# BSPD.net
KiCad netlist of a schematic drawn in EAGLE
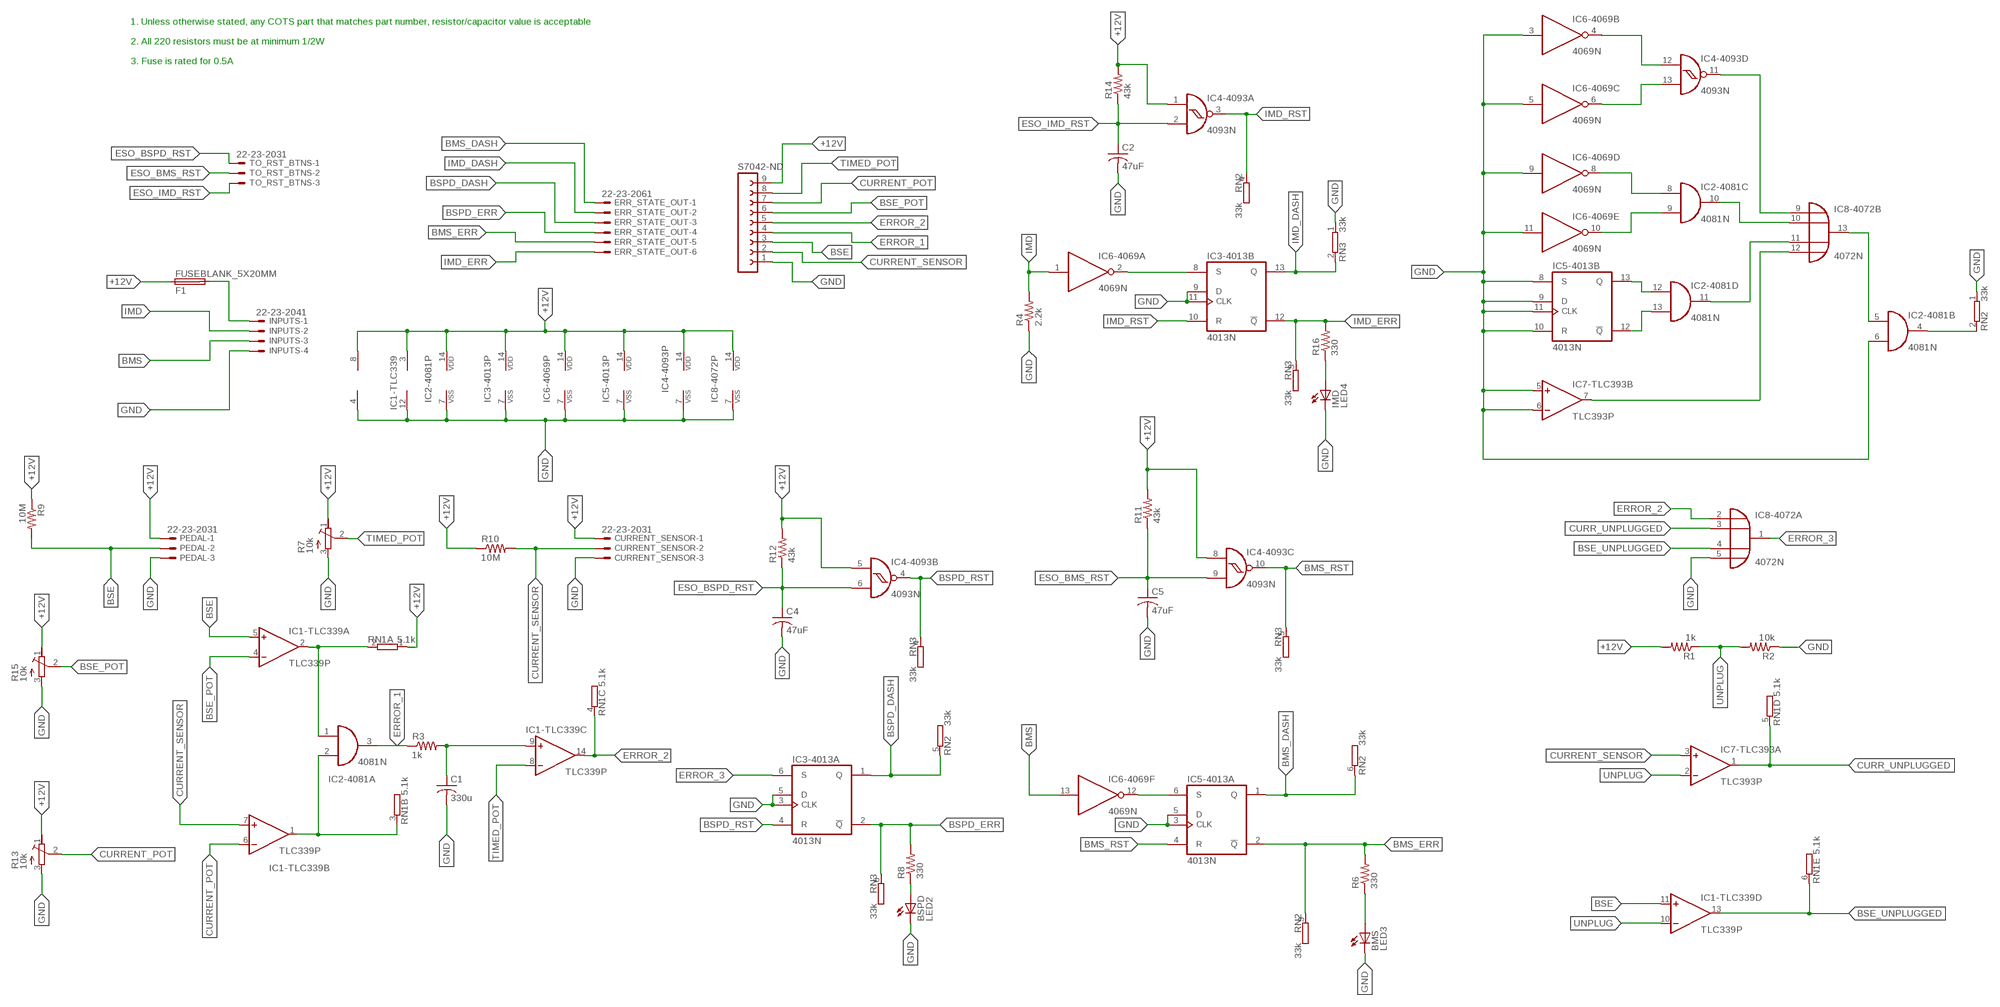
[diagram p0: schematic, sheet 1]

(export (version "E")
  (design (tool "Eeschema 10.0.6"))
  (components
    (comp (ref "BMS")
      (value "LED3")
      (footprint "eagle-import:LED3MM")
      (libsource (lib "eagle-import") (part "LED3MM"))
    )
    (comp (ref "BSPD")
      (value "LED2")
      (footprint "eagle-import:LED3MM")
      (libsource (lib "eagle-import") (part "LED3MM"))
    )
    (comp (ref "C1")
      (value "330u")
      (footprint "eagle-import:C225-108X268")
      (libsource (lib "eagle-import") (part "C-US225-108X268"))
    )
    (comp (ref "C2")
      (value "47uF")
      (footprint "eagle-import:C050-024X044")
      (libsource (lib "eagle-import") (part "C-US050-024X044"))
    )
    (comp (ref "C4")
      (value "47uF")
      (footprint "eagle-import:C050-024X044")
      (libsource (lib "eagle-import") (part "C-US050-024X044"))
    )
    (comp (ref "C5")
      (value "47uF")
      (footprint "eagle-import:C050-024X044")
      (libsource (lib "eagle-import") (part "C-US050-024X044"))
    )
    (comp (ref "CURRENT_SENSOR")
      (value "22-23-2031")
      (footprint "eagle-import:22-23-2031")
      (fields (field (name "MF") "MOLEX"))
      (libsource (lib "eagle-import") (part "22-23-2031"))
    )
    (comp (ref "ERR_STATE_OUT")
      (value "22-23-2061")
      (footprint "eagle-import:22-23-2061")
      (fields (field (name "MF") "MOLEX"))
      (libsource (lib "eagle-import") (part "22-23-2061"))
    )
    (comp (ref "F1")
      (value "FUSEBLANK_5X20MM")
      (footprint "eagle-import:FUSE_HOLDER_5X20MM")
      (libsource (lib "eagle-import") (part "FUSEBLANK_5X20MM"))
    )
    (comp (ref "IC1-TLC339")
      (value "TLC339P")
      (footprint "eagle-import:DIL14")
      (libsource (lib "eagle-import") (part "TLC339P"))
    )
    (comp (ref "IC2-4081")
      (value "4081N")
      (footprint "eagle-import:DIL14")
      (libsource (lib "eagle-import") (part "4081N"))
    )
    (comp (ref "IC3-4013")
      (value "4013N")
      (footprint "eagle-import:DIL14")
      (libsource (lib "eagle-import") (part "4013N"))
    )
    (comp (ref "IC4-4093")
      (value "4093N")
      (footprint "eagle-import:DIL14")
      (libsource (lib "eagle-import") (part "4093N"))
    )
    (comp (ref "IC5-4013")
      (value "4013N")
      (footprint "eagle-import:DIL14")
      (libsource (lib "eagle-import") (part "4013N"))
    )
    (comp (ref "IC6-4069")
      (value "4069N")
      (footprint "eagle-import:DIL14")
      (libsource (lib "eagle-import") (part "4069N"))
    )
    (comp (ref "IC7-TLC393")
      (value "TLC393P")
      (footprint "eagle-import:DIL08")
      (libsource (lib "eagle-import") (part "TLC393P"))
    )
    (comp (ref "IC8-4072")
      (value "4072N")
      (footprint "eagle-import:DIL14")
      (libsource (lib "eagle-import") (part "4072N"))
    )
    (comp (ref "IMD")
      (value "LED4")
      (footprint "eagle-import:LED3MM")
      (libsource (lib "eagle-import") (part "LED3MM"))
    )
    (comp (ref "INPUTS")
      (value "22-23-2041")
      (footprint "eagle-import:22-23-2041")
      (fields (field (name "MF") "MOLEX"))
      (libsource (lib "eagle-import") (part "22-23-2041"))
    )
    (comp (ref "PEDAL")
      (value "22-23-2031")
      (footprint "eagle-import:22-23-2031")
      (fields (field (name "MF") "MOLEX"))
      (libsource (lib "eagle-import") (part "22-23-2031"))
    )
    (comp (ref "R1")
      (value "1k")
      (footprint "eagle-import:0207_12")
      (libsource (lib "eagle-import") (part "R-US_0207/12"))
    )
    (comp (ref "R2")
      (value "10k")
      (footprint "eagle-import:0207_12")
      (libsource (lib "eagle-import") (part "R-US_0207/12"))
    )
    (comp (ref "R3")
      (value "1k")
      (footprint "eagle-import:0207_12")
      (libsource (lib "eagle-import") (part "R-US_0207/12"))
    )
    (comp (ref "R4")
      (value "2.2k")
      (footprint "eagle-import:0207_12")
      (libsource (lib "eagle-import") (part "R-US_0207/12"))
    )
    (comp (ref "R6")
      (value "330")
      (footprint "eagle-import:0207_12")
      (libsource (lib "eagle-import") (part "R-US_0207/12"))
    )
    (comp (ref "R7")
      (value "10k")
      (footprint "eagle-import:RTRIM3006P")
      (libsource (lib "eagle-import") (part "R-TRIMM3006P"))
    )
    (comp (ref "R8")
      (value "330")
      (footprint "eagle-import:0207_12")
      (libsource (lib "eagle-import") (part "R-US_0207/12"))
    )
    (comp (ref "R9")
      (value "10M")
      (footprint "eagle-import:0207_12")
      (libsource (lib "eagle-import") (part "R-US_0207/12"))
    )
    (comp (ref "R10")
      (value "10M")
      (footprint "eagle-import:0207_12")
      (libsource (lib "eagle-import") (part "R-US_0207/12"))
    )
    (comp (ref "R11")
      (value "43k")
      (footprint "eagle-import:0207_12")
      (libsource (lib "eagle-import") (part "R-US_0207/12"))
    )
    (comp (ref "R12")
      (value "43k")
      (footprint "eagle-import:0207_12")
      (libsource (lib "eagle-import") (part "R-US_0207/12"))
    )
    (comp (ref "R13")
      (value "10k")
      (footprint "eagle-import:RTRIM3006P")
      (libsource (lib "eagle-import") (part "R-TRIMM3006P"))
    )
    (comp (ref "R14")
      (value "43k")
      (footprint "eagle-import:0207_12")
      (libsource (lib "eagle-import") (part "R-US_0207/12"))
    )
    (comp (ref "R15")
      (value "10k")
      (footprint "eagle-import:RTRIM3006P")
      (libsource (lib "eagle-import") (part "R-TRIMM3006P"))
    )
    (comp (ref "R16")
      (value "330")
      (footprint "eagle-import:0207_12")
      (libsource (lib "eagle-import") (part "R-US_0207/12"))
    )
    (comp (ref "RN1")
      (value "5.1k")
      (footprint "eagle-import:SIL6")
      (libsource (lib "eagle-import") (part "GE05R"))
    )
    (comp (ref "RN2")
      (value "33k")
      (footprint "eagle-import:SIL6")
      (libsource (lib "eagle-import") (part "GE05RP"))
    )
    (comp (ref "RN3")
      (value "33k")
      (footprint "eagle-import:SIL6")
      (libsource (lib "eagle-import") (part "GE05RP"))
    )
    (comp (ref "S7042-ND")
      (value "FE09W")
      (footprint "eagle-import:FE09W")
      (libsource (lib "eagle-import") (part "FE09W"))
    )
    (comp (ref "TO_RST_BTNS")
      (value "22-23-2031")
      (footprint "eagle-import:22-23-2031")
      (fields (field (name "MF") "MOLEX"))
      (libsource (lib "eagle-import") (part "22-23-2031"))
    )
  )
  (nets
    (net (code "1") (name "+12V") (class "Default")
      (node (ref "CURRENT_SENSOR") (pin "1") (pinfunction "S_1") (pintype "passive"))
      (node (ref "F1") (pin "1") (pinfunction "1_1") (pintype "passive"))
      (node (ref "IC1-TLC339") (pin "3") (pinfunction "V+_3") (pintype "power_in"))
      (node (ref "IC2-4081") (pin "14") (pinfunction "VDD_14") (pintype "power_in"))
      (node (ref "IC3-4013") (pin "14") (pinfunction "VDD_14") (pintype "power_in"))
      (node (ref "IC4-4093") (pin "1") (pinfunction "I0_1") (pintype "input"))
      (node (ref "IC4-4093") (pin "14") (pinfunction "VDD_14") (pintype "power_in"))
      (node (ref "IC4-4093") (pin "5") (pinfunction "I0_5") (pintype "input"))
      (node (ref "IC4-4093") (pin "8") (pinfunction "I0_8") (pintype "input"))
      (node (ref "IC5-4013") (pin "14") (pinfunction "VDD_14") (pintype "power_in"))
      (node (ref "IC6-4069") (pin "14") (pinfunction "VDD_14") (pintype "power_in"))
      (node (ref "IC7-TLC393") (pin "8") (pinfunction "V+_8") (pintype "power_in"))
      (node (ref "IC8-4072") (pin "14") (pinfunction "VDD_14") (pintype "power_in"))
      (node (ref "PEDAL") (pin "1") (pinfunction "S_1") (pintype "passive"))
      (node (ref "R1") (pin "2") (pinfunction "2_2") (pintype "passive"))
      (node (ref "R10") (pin "1") (pinfunction "1_1") (pintype "passive"))
      (node (ref "R11") (pin "2") (pinfunction "2_2") (pintype "passive"))
      (node (ref "R12") (pin "2") (pinfunction "2_2") (pintype "passive"))
      (node (ref "R13") (pin "1") (pinfunction "E_1") (pintype "passive"))
      (node (ref "R14") (pin "2") (pinfunction "2_2") (pintype "passive"))
      (node (ref "R15") (pin "1") (pinfunction "E_1") (pintype "passive"))
      (node (ref "R7") (pin "1") (pinfunction "E_1") (pintype "passive"))
      (node (ref "R9") (pin "1") (pinfunction "1_1") (pintype "passive"))
      (node (ref "RN1") (pin "1") (pinfunction "1_1") (pintype "passive"))
      (node (ref "S7042-ND") (pin "9") (pinfunction "9_9") (pintype "passive"))
    )
    (net (code "2") (name "BMS") (class "Default")
      (node (ref "IC6-4069") (pin "13") (pinfunction "I_13") (pintype "input"))
      (node (ref "INPUTS") (pin "3") (pinfunction "S_3") (pintype "passive"))
    )
    (net (code "3") (name "BMS_DASH") (class "Default")
      (node (ref "ERR_STATE_OUT") (pin "1") (pinfunction "S_1") (pintype "passive"))
      (node (ref "IC5-4013") (pin "1") (pinfunction "Q_1") (pintype "output"))
      (node (ref "RN2") (pin "6") (pinfunction "2_6") (pintype "passive"))
    )
    (net (code "4") (name "BMS_ERR") (class "Default")
      (node (ref "ERR_STATE_OUT") (pin "5") (pinfunction "S_5") (pintype "passive"))
      (node (ref "IC5-4013") (pin "2") (pinfunction "~{Q}_2") (pintype "output"))
      (node (ref "R6") (pin "2") (pinfunction "2_2") (pintype "passive"))
      (node (ref "RN2") (pin "3") (pinfunction "2_3") (pintype "passive"))
    )
    (net (code "5") (name "BMS_RST") (class "Default")
      (node (ref "IC4-4093") (pin "10") (pinfunction "O_10") (pintype "output"))
      (node (ref "IC5-4013") (pin "4") (pinfunction "R_4") (pintype "input"))
      (node (ref "RN3") (pin "5") (pinfunction "2_5") (pintype "passive"))
    )
    (net (code "6") (name "BSE") (class "Default")
      (node (ref "IC1-TLC339") (pin "11") (pinfunction "+IN_11") (pintype "input"))
      (node (ref "IC1-TLC339") (pin "5") (pinfunction "+IN_5") (pintype "input"))
      (node (ref "PEDAL") (pin "2") (pinfunction "S_2") (pintype "passive"))
      (node (ref "R9") (pin "2") (pinfunction "2_2") (pintype "passive"))
      (node (ref "S7042-ND") (pin "3") (pinfunction "3_3") (pintype "passive"))
    )
    (net (code "7") (name "BSE_POT") (class "Default")
      (node (ref "IC1-TLC339") (pin "4") (pinfunction "-IN_4") (pintype "input"))
      (node (ref "R15") (pin "2") (pinfunction "S_2") (pintype "passive"))
      (node (ref "S7042-ND") (pin "6") (pinfunction "6_6") (pintype "passive"))
    )
    (net (code "8") (name "BSE_UNPLUGGED") (class "Default")
      (node (ref "IC1-TLC339") (pin "13") (pinfunction "OUT_13") (pintype "output"))
      (node (ref "IC8-4072") (pin "4") (pinfunction "I2_4") (pintype "input"))
      (node (ref "RN1") (pin "6") (pinfunction "2_6") (pintype "passive"))
    )
    (net (code "9") (name "BSPD_DASH") (class "Default")
      (node (ref "ERR_STATE_OUT") (pin "3") (pinfunction "S_3") (pintype "passive"))
      (node (ref "IC3-4013") (pin "1") (pinfunction "Q_1") (pintype "output"))
      (node (ref "RN2") (pin "5") (pinfunction "2_5") (pintype "passive"))
    )
    (net (code "10") (name "BSPD_ERR") (class "Default")
      (node (ref "ERR_STATE_OUT") (pin "4") (pinfunction "S_4") (pintype "passive"))
      (node (ref "IC3-4013") (pin "2") (pinfunction "~{Q}_2") (pintype "output"))
      (node (ref "R8") (pin "2") (pinfunction "2_2") (pintype "passive"))
      (node (ref "RN3") (pin "6") (pinfunction "2_6") (pintype "passive"))
    )
    (net (code "11") (name "BSPD_RST") (class "Default")
      (node (ref "IC3-4013") (pin "4") (pinfunction "R_4") (pintype "input"))
      (node (ref "IC4-4093") (pin "4") (pinfunction "O_4") (pintype "output"))
      (node (ref "RN3") (pin "4") (pinfunction "2_4") (pintype "passive"))
    )
    (net (code "12") (name "CURRENT_POT") (class "Default")
      (node (ref "IC1-TLC339") (pin "6") (pinfunction "-IN_6") (pintype "input"))
      (node (ref "R13") (pin "2") (pinfunction "S_2") (pintype "passive"))
      (node (ref "S7042-ND") (pin "7") (pinfunction "7_7") (pintype "passive"))
    )
    (net (code "13") (name "CURRENT_SENSOR") (class "Default")
      (node (ref "CURRENT_SENSOR") (pin "2") (pinfunction "S_2") (pintype "passive"))
      (node (ref "IC1-TLC339") (pin "7") (pinfunction "+IN_7") (pintype "input"))
      (node (ref "IC7-TLC393") (pin "3") (pinfunction "+IN_3") (pintype "input"))
      (node (ref "R10") (pin "2") (pinfunction "2_2") (pintype "passive"))
      (node (ref "S7042-ND") (pin "2") (pinfunction "2_2") (pintype "passive"))
    )
    (net (code "14") (name "CURR_UNPLUGGED") (class "Default")
      (node (ref "IC7-TLC393") (pin "1") (pinfunction "OUT_1") (pintype "output"))
      (node (ref "IC8-4072") (pin "3") (pinfunction "I1_3") (pintype "input"))
      (node (ref "RN1") (pin "5") (pinfunction "2_5") (pintype "passive"))
    )
    (net (code "15") (name "ERROR_1") (class "Default")
      (node (ref "IC2-4081") (pin "3") (pinfunction "O_3") (pintype "output"))
      (node (ref "R3") (pin "1") (pinfunction "1_1") (pintype "passive"))
      (node (ref "S7042-ND") (pin "4") (pinfunction "4_4") (pintype "passive"))
    )
    (net (code "16") (name "ERROR_2") (class "Default")
      (node (ref "IC1-TLC339") (pin "14") (pinfunction "OUT_14") (pintype "output"))
      (node (ref "IC8-4072") (pin "2") (pinfunction "I0_2") (pintype "input"))
      (node (ref "RN1") (pin "4") (pinfunction "2_4") (pintype "passive"))
      (node (ref "S7042-ND") (pin "5") (pinfunction "5_5") (pintype "passive"))
    )
    (net (code "17") (name "ERROR_3") (class "Default")
      (node (ref "IC3-4013") (pin "6") (pinfunction "S_6") (pintype "input"))
      (node (ref "IC8-4072") (pin "1") (pinfunction "O_1") (pintype "output"))
    )
    (net (code "18") (name "ESO_BMS_RST") (class "Default")
      (node (ref "C5") (pin "1") (pinfunction "1_1") (pintype "passive"))
      (node (ref "IC4-4093") (pin "9") (pinfunction "I1_9") (pintype "input"))
      (node (ref "R11") (pin "1") (pinfunction "1_1") (pintype "passive"))
      (node (ref "TO_RST_BTNS") (pin "2") (pinfunction "S_2") (pintype "passive"))
    )
    (net (code "19") (name "ESO_BSPD_RST") (class "Default")
      (node (ref "C4") (pin "1") (pinfunction "1_1") (pintype "passive"))
      (node (ref "IC4-4093") (pin "6") (pinfunction "I1_6") (pintype "input"))
      (node (ref "R12") (pin "1") (pinfunction "1_1") (pintype "passive"))
      (node (ref "TO_RST_BTNS") (pin "1") (pinfunction "S_1") (pintype "passive"))
    )
    (net (code "20") (name "ESO_IMD_RST") (class "Default")
      (node (ref "C2") (pin "1") (pinfunction "1_1") (pintype "passive"))
      (node (ref "IC4-4093") (pin "2") (pinfunction "I1_2") (pintype "input"))
      (node (ref "R14") (pin "1") (pinfunction "1_1") (pintype "passive"))
      (node (ref "TO_RST_BTNS") (pin "3") (pinfunction "S_3") (pintype "passive"))
    )
    (net (code "21") (name "GND") (class "Default")
      (node (ref "BMS") (pin "K") (pinfunction "C_K") (pintype "passive"))
      (node (ref "BSPD") (pin "K") (pinfunction "C_K") (pintype "passive"))
      (node (ref "C1") (pin "2") (pinfunction "2_2") (pintype "passive"))
      (node (ref "C2") (pin "2") (pinfunction "2_2") (pintype "passive"))
      (node (ref "C4") (pin "2") (pinfunction "2_2") (pintype "passive"))
      (node (ref "C5") (pin "2") (pinfunction "2_2") (pintype "passive"))
      (node (ref "CURRENT_SENSOR") (pin "3") (pinfunction "S_3") (pintype "passive"))
      (node (ref "IC1-TLC339") (pin "12") (pinfunction "V-_12") (pintype "power_in"))
      (node (ref "IC2-4081") (pin "6") (pinfunction "I1_6") (pintype "input"))
      (node (ref "IC2-4081") (pin "7") (pinfunction "VSS_7") (pintype "power_in"))
      (node (ref "IC3-4013") (pin "11") (pinfunction "CLK_11") (pintype "input"))
      (node (ref "IC3-4013") (pin "3") (pinfunction "CLK_3") (pintype "input"))
      (node (ref "IC3-4013") (pin "5") (pinfunction "D_5") (pintype "input"))
      (node (ref "IC3-4013") (pin "7") (pinfunction "VSS_7") (pintype "power_in"))
      (node (ref "IC3-4013") (pin "9") (pinfunction "D_9") (pintype "input"))
      (node (ref "IC4-4093") (pin "7") (pinfunction "VSS_7") (pintype "power_in"))
      (node (ref "IC5-4013") (pin "10") (pinfunction "R_10") (pintype "input"))
      (node (ref "IC5-4013") (pin "11") (pinfunction "CLK_11") (pintype "input"))
      (node (ref "IC5-4013") (pin "3") (pinfunction "CLK_3") (pintype "input"))
      (node (ref "IC5-4013") (pin "5") (pinfunction "D_5") (pintype "input"))
      (node (ref "IC5-4013") (pin "7") (pinfunction "VSS_7") (pintype "power_in"))
      (node (ref "IC5-4013") (pin "8") (pinfunction "S_8") (pintype "input"))
      (node (ref "IC5-4013") (pin "9") (pinfunction "D_9") (pintype "input"))
      (node (ref "IC6-4069") (pin "11") (pinfunction "I_11") (pintype "input"))
      (node (ref "IC6-4069") (pin "3") (pinfunction "I_3") (pintype "input"))
      (node (ref "IC6-4069") (pin "5") (pinfunction "I_5") (pintype "input"))
      (node (ref "IC6-4069") (pin "7") (pinfunction "VSS_7") (pintype "power_in"))
      (node (ref "IC6-4069") (pin "9") (pinfunction "I_9") (pintype "input"))
      (node (ref "IC7-TLC393") (pin "4") (pinfunction "V-_4") (pintype "power_in"))
      (node (ref "IC7-TLC393") (pin "5") (pinfunction "+IN_5") (pintype "input"))
      (node (ref "IC7-TLC393") (pin "6") (pinfunction "-IN_6") (pintype "input"))
      (node (ref "IC8-4072") (pin "5") (pinfunction "I3_5") (pintype "input"))
      (node (ref "IC8-4072") (pin "7") (pinfunction "VSS_7") (pintype "power_in"))
      (node (ref "IMD") (pin "K") (pinfunction "C_K") (pintype "passive"))
      (node (ref "INPUTS") (pin "4") (pinfunction "S_4") (pintype "passive"))
      (node (ref "PEDAL") (pin "3") (pinfunction "S_3") (pintype "passive"))
      (node (ref "R13") (pin "3") (pinfunction "A_3") (pintype "passive"))
      (node (ref "R15") (pin "3") (pinfunction "A_3") (pintype "passive"))
      (node (ref "R2") (pin "1") (pinfunction "1_1") (pintype "passive"))
      (node (ref "R4") (pin "1") (pinfunction "1_1") (pintype "passive"))
      (node (ref "R7") (pin "3") (pinfunction "A_3") (pintype "passive"))
      (node (ref "RN2") (pin "1") (pinfunction "1_1") (pintype "passive"))
      (node (ref "RN3") (pin "1") (pinfunction "1_1") (pintype "passive"))
      (node (ref "S7042-ND") (pin "1") (pinfunction "1_1") (pintype "passive"))
    )
    (net (code "22") (name "IMD") (class "Default")
      (node (ref "IC6-4069") (pin "1") (pinfunction "I_1") (pintype "input"))
      (node (ref "INPUTS") (pin "2") (pinfunction "S_2") (pintype "passive"))
      (node (ref "R4") (pin "2") (pinfunction "2_2") (pintype "passive"))
    )
    (net (code "23") (name "IMD_DASH") (class "Default")
      (node (ref "ERR_STATE_OUT") (pin "2") (pinfunction "S_2") (pintype "passive"))
      (node (ref "IC3-4013") (pin "13") (pinfunction "Q_13") (pintype "output"))
      (node (ref "RN3") (pin "2") (pinfunction "2_2") (pintype "passive"))
    )
    (net (code "24") (name "IMD_ERR") (class "Default")
      (node (ref "ERR_STATE_OUT") (pin "6") (pinfunction "S_6") (pintype "passive"))
      (node (ref "IC3-4013") (pin "12") (pinfunction "~{Q}_12") (pintype "output"))
      (node (ref "R16") (pin "2") (pinfunction "2_2") (pintype "passive"))
      (node (ref "RN3") (pin "3") (pinfunction "2_3") (pintype "passive"))
    )
    (net (code "25") (name "IMD_RST") (class "Default")
      (node (ref "IC3-4013") (pin "10") (pinfunction "R_10") (pintype "input"))
      (node (ref "IC4-4093") (pin "3") (pinfunction "O_3") (pintype "output"))
      (node (ref "RN2") (pin "4") (pinfunction "2_4") (pintype "passive"))
    )
    (net (code "26") (name "Net-(BMS-PadA)") (class "Default")
      (node (ref "BMS") (pin "A") (pinfunction "A_A") (pintype "passive"))
      (node (ref "R6") (pin "1") (pinfunction "1_1") (pintype "passive"))
    )
    (net (code "27") (name "Net-(BSPD-PadA)") (class "Default")
      (node (ref "BSPD") (pin "A") (pinfunction "A_A") (pintype "passive"))
      (node (ref "R8") (pin "1") (pinfunction "1_1") (pintype "passive"))
    )
    (net (code "28") (name "Net-(IC1-TLC339A-OUT)") (class "Default")
      (node (ref "IC1-TLC339") (pin "2") (pinfunction "OUT_2") (pintype "output"))
      (node (ref "IC2-4081") (pin "1") (pinfunction "I0_1") (pintype "input"))
      (node (ref "RN1") (pin "2") (pinfunction "2_2") (pintype "passive"))
    )
    (net (code "29") (name "Net-(IC1-TLC339B-OUT)") (class "Default")
      (node (ref "IC1-TLC339") (pin "1") (pinfunction "OUT_1") (pintype "output"))
      (node (ref "IC2-4081") (pin "2") (pinfunction "I1_2") (pintype "input"))
      (node (ref "RN1") (pin "3") (pinfunction "2_3") (pintype "passive"))
    )
    (net (code "30") (name "Net-(IC1-TLC339C-+IN)") (class "Default")
      (node (ref "C1") (pin "1") (pinfunction "1_1") (pintype "passive"))
      (node (ref "IC1-TLC339") (pin "9") (pinfunction "+IN_9") (pintype "input"))
      (node (ref "R3") (pin "2") (pinfunction "2_2") (pintype "passive"))
    )
    (net (code "31") (name "Net-(IC2-4081B-I0)") (class "Default")
      (node (ref "IC2-4081") (pin "5") (pinfunction "I0_5") (pintype "input"))
      (node (ref "IC8-4072") (pin "13") (pinfunction "O_13") (pintype "output"))
    )
    (net (code "32") (name "Net-(IC2-4081B-O)") (class "Default")
      (node (ref "IC2-4081") (pin "4") (pinfunction "O_4") (pintype "output"))
      (node (ref "RN2") (pin "2") (pinfunction "2_2") (pintype "passive"))
    )
    (net (code "33") (name "Net-(IC2-4081C-I0)") (class "Default")
      (node (ref "IC2-4081") (pin "8") (pinfunction "I0_8") (pintype "input"))
      (node (ref "IC6-4069") (pin "8") (pinfunction "O_8") (pintype "output"))
    )
    (net (code "34") (name "Net-(IC2-4081C-I1)") (class "Default")
      (node (ref "IC2-4081") (pin "9") (pinfunction "I1_9") (pintype "input"))
      (node (ref "IC6-4069") (pin "10") (pinfunction "O_10") (pintype "output"))
    )
    (net (code "35") (name "Net-(IC2-4081C-O)") (class "Default")
      (node (ref "IC2-4081") (pin "10") (pinfunction "O_10") (pintype "output"))
      (node (ref "IC8-4072") (pin "10") (pinfunction "I1_10") (pintype "input"))
    )
    (net (code "36") (name "Net-(IC2-4081D-I0)") (class "Default")
      (node (ref "IC2-4081") (pin "12") (pinfunction "I0_12") (pintype "input"))
      (node (ref "IC5-4013") (pin "13") (pinfunction "Q_13") (pintype "output"))
    )
    (net (code "37") (name "Net-(IC2-4081D-I1)") (class "Default")
      (node (ref "IC2-4081") (pin "13") (pinfunction "I1_13") (pintype "input"))
      (node (ref "IC5-4013") (pin "12") (pinfunction "~{Q}_12") (pintype "output"))
    )
    (net (code "38") (name "Net-(IC2-4081D-O)") (class "Default")
      (node (ref "IC2-4081") (pin "11") (pinfunction "O_11") (pintype "output"))
      (node (ref "IC8-4072") (pin "11") (pinfunction "I2_11") (pintype "input"))
    )
    (net (code "39") (name "Net-(IC3-4013B-S)") (class "Default")
      (node (ref "IC3-4013") (pin "8") (pinfunction "S_8") (pintype "input"))
      (node (ref "IC6-4069") (pin "2") (pinfunction "O_2") (pintype "output"))
    )
    (net (code "40") (name "Net-(IC4-4093D-I0)") (class "Default")
      (node (ref "IC4-4093") (pin "12") (pinfunction "I0_12") (pintype "input"))
      (node (ref "IC6-4069") (pin "4") (pinfunction "O_4") (pintype "output"))
    )
    (net (code "41") (name "Net-(IC4-4093D-I1)") (class "Default")
      (node (ref "IC4-4093") (pin "13") (pinfunction "I1_13") (pintype "input"))
      (node (ref "IC6-4069") (pin "6") (pinfunction "O_6") (pintype "output"))
    )
    (net (code "42") (name "Net-(IC4-4093D-O)") (class "Default")
      (node (ref "IC4-4093") (pin "11") (pinfunction "O_11") (pintype "output"))
      (node (ref "IC8-4072") (pin "9") (pinfunction "I0_9") (pintype "input"))
    )
    (net (code "43") (name "Net-(IC5-4013A-S)") (class "Default")
      (node (ref "IC5-4013") (pin "6") (pinfunction "S_6") (pintype "input"))
      (node (ref "IC6-4069") (pin "12") (pinfunction "O_12") (pintype "output"))
    )
    (net (code "44") (name "Net-(IC7-TLC393B-OUT)") (class "Default")
      (node (ref "IC7-TLC393") (pin "7") (pinfunction "OUT_7") (pintype "output"))
      (node (ref "IC8-4072") (pin "12") (pinfunction "I3_12") (pintype "input"))
    )
    (net (code "45") (name "Net-(IMD-PadA)") (class "Default")
      (node (ref "IMD") (pin "A") (pinfunction "A_A") (pintype "passive"))
      (node (ref "R16") (pin "1") (pinfunction "1_1") (pintype "passive"))
    )
    (net (code "46") (name "Net-(INPUTSA-S)") (class "Default")
      (node (ref "F1") (pin "2") (pinfunction "2_2") (pintype "passive"))
      (node (ref "INPUTS") (pin "1") (pinfunction "S_1") (pintype "passive"))
    )
    (net (code "47") (name "TIMED_POT") (class "Default")
      (node (ref "IC1-TLC339") (pin "8") (pinfunction "-IN_8") (pintype "input"))
      (node (ref "R7") (pin "2") (pinfunction "S_2") (pintype "passive"))
      (node (ref "S7042-ND") (pin "8") (pinfunction "8_8") (pintype "passive"))
    )
    (net (code "48") (name "UNPLUG") (class "Default")
      (node (ref "IC1-TLC339") (pin "10") (pinfunction "-IN_10") (pintype "input"))
      (node (ref "IC7-TLC393") (pin "2") (pinfunction "-IN_2") (pintype "input"))
      (node (ref "R1") (pin "1") (pinfunction "1_1") (pintype "passive"))
      (node (ref "R2") (pin "2") (pinfunction "2_2") (pintype "passive"))
    )
  )
)
